# OPAMP_Combo_Schema.net
KiCad netlist of a schematic drawn in Altium Designer
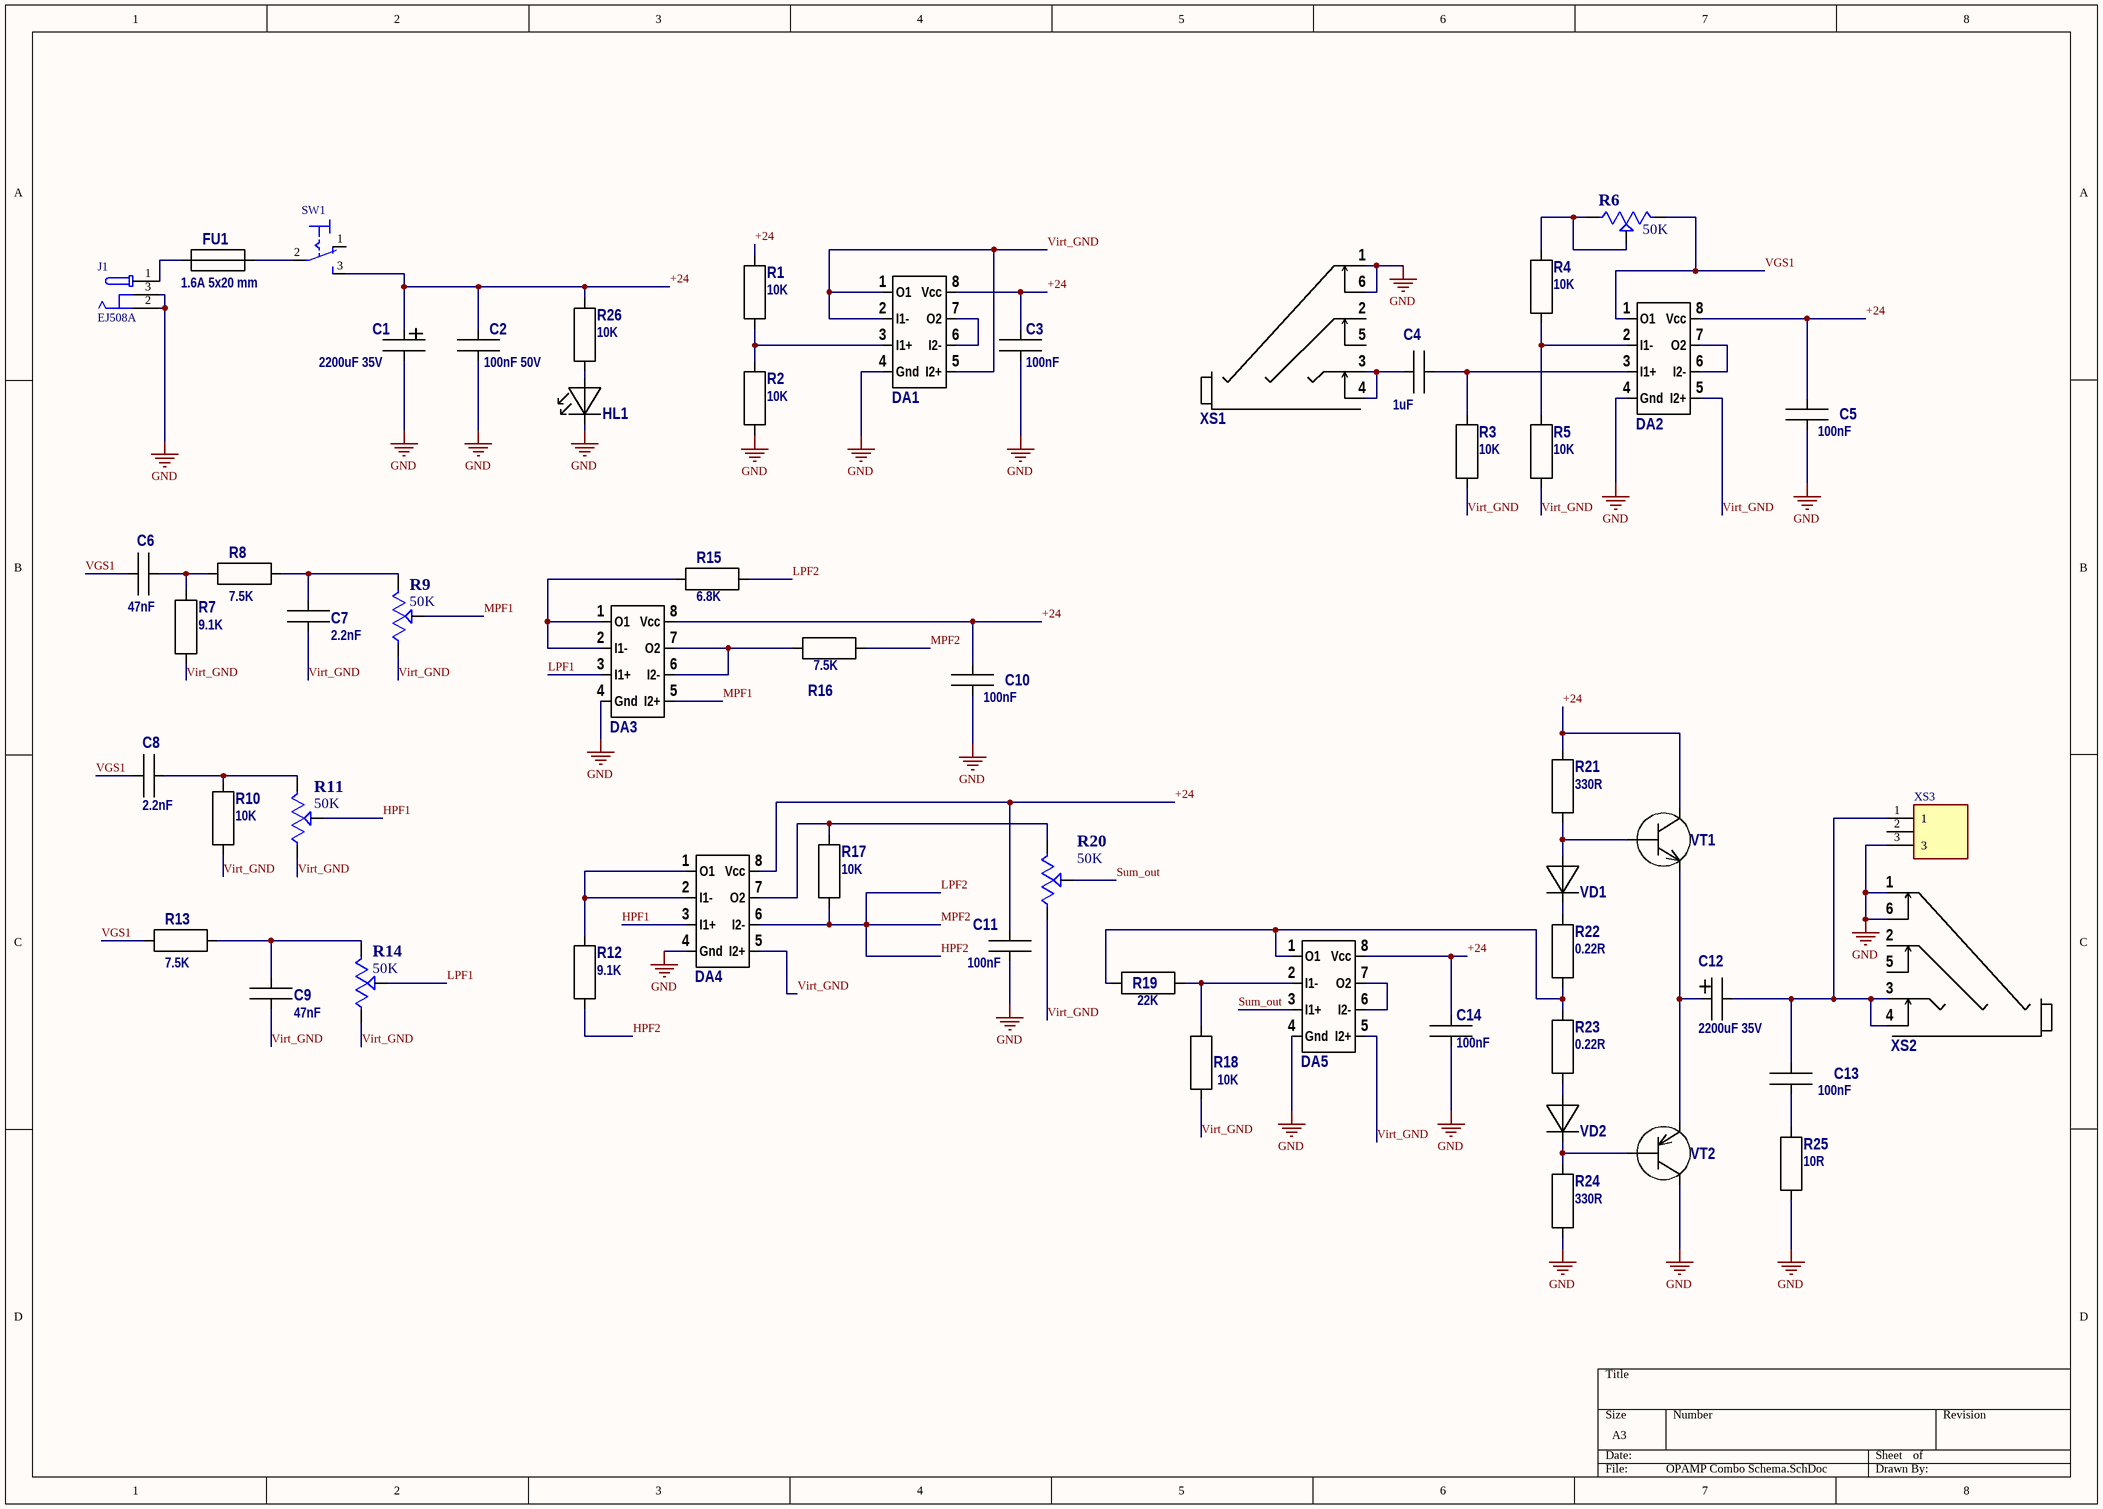
[diagram p0: OPAMP Combo Schema.SchDoc]

(export (version "E")
  (design (tool "Eeschema 10.0.6"))
  (components
    (comp (ref "C1")
      (value "2200uF 35V")
      (footprint "capr- 7.5D16.5H35")
      (description "Конденсатор алюминиевый радиальный")
      (libsource (lib "RLC V7.1_BVI") (part "C Al R"))
    )
    (comp (ref "C2")
      (value "100nF 50V")
      (footprint "C__s 5-d 8-t4")
      (description "Конденсатор керамика")
      (libsource (lib "RLC V7.1_BVI") (part "C_Disk"))
    )
    (comp (ref "C3")
      (value "100nF")
      (footprint "Cap 0805 3D")
      (description "Конденсатор керамика")
      (libsource (lib "RLC V7.1_BVI") (part "C"))
    )
    (comp (ref "C4")
      (value "1uF")
      (footprint "C__s 5-d 5.5-t4")
      (description "Конденсатор керамика")
      (libsource (lib "RLC V7.1_BVI") (part "C_Disk"))
    )
    (comp (ref "C5")
      (value "100nF")
      (footprint "Cap 0805 3D")
      (description "Конденсатор керамика")
      (libsource (lib "RLC V7.1_BVI") (part "C"))
    )
    (comp (ref "C6")
      (value "47nF")
      (footprint "C__s10-d12.4-t4")
      (description "Конденсатор керамика")
      (libsource (lib "RLC V7.1_BVI") (part "C_Disk"))
    )
    (comp (ref "C7")
      (value "2.2nF")
      (footprint "C__s10-d12.4-t4")
      (description "Конденсатор керамика")
      (libsource (lib "RLC V7.1_BVI") (part "C_Disk"))
    )
    (comp (ref "C8")
      (value "2.2nF")
      (footprint "C__s10-d12.4-t4")
      (description "Конденсатор керамика")
      (libsource (lib "RLC V7.1_BVI") (part "C_Disk"))
    )
    (comp (ref "C9")
      (value "47nF")
      (footprint "C__s10-d12.4-t4")
      (description "Конденсатор керамика")
      (libsource (lib "RLC V7.1_BVI") (part "C_Disk"))
    )
    (comp (ref "C10")
      (value "100nF")
      (footprint "Cap 0805 3D")
      (description "Конденсатор керамика")
      (libsource (lib "RLC V7.1_BVI") (part "C"))
    )
    (comp (ref "C11")
      (value "100nF")
      (footprint "Cap 0805 3D")
      (description "Конденсатор керамика")
      (libsource (lib "RLC V7.1_BVI") (part "C"))
    )
    (comp (ref "C12")
      (value "2200uF 35V")
      (footprint "capr- 7.5D16.5H35")
      (description "Конденсатор алюминиевый радиальный")
      (libsource (lib "RLC V7.1_BVI") (part "C Al R"))
    )
    (comp (ref "C13")
      (value "100nF")
      (footprint "C__s 5-d 7-t4")
      (description "Конденсатор керамика")
      (libsource (lib "RLC V7.1_BVI") (part "C_Disk"))
    )
    (comp (ref "C14")
      (value "100nF")
      (footprint "Cap 0805 3D")
      (description "Конденсатор керамика")
      (libsource (lib "RLC V7.1_BVI") (part "C"))
    )
    (comp (ref "DA1")
      (value "ОУ х 2 (1)")
      (footprint "DIP-8")
      (description "NJM4558/4559  LM158х   LM258х   LM358х   LM2904х  TL072х   NE5532x   SA5532x  и другие")
      (libsource (lib "DA V5.1_BVI") (part "ОУ х 2 (1)"))
    )
    (comp (ref "DA2")
      (value "ОУ х 2 (1)")
      (footprint "DIP-8")
      (description "NJM4558/4559  LM158х   LM258х   LM358х   LM2904х  TL072х   NE5532x   SA5532x  и другие")
      (libsource (lib "DA V5.1_BVI") (part "ОУ х 2 (1)"))
    )
    (comp (ref "DA3")
      (value "ОУ х 2 (1)")
      (footprint "DIP-8")
      (description "NJM4558/4559  LM158х   LM258х   LM358х   LM2904х  TL072х   NE5532x   SA5532x  и другие")
      (libsource (lib "DA V5.1_BVI") (part "ОУ х 2 (1)"))
    )
    (comp (ref "DA4")
      (value "ОУ х 2 (1)")
      (footprint "DIP-8")
      (description "NJM4558/4559  LM158х   LM258х   LM358х   LM2904х  TL072х   NE5532x   SA5532x  и другие")
      (libsource (lib "DA V5.1_BVI") (part "ОУ х 2 (1)"))
    )
    (comp (ref "DA5")
      (value "ОУ х 2 (1)")
      (footprint "DIP-8")
      (description "NJM4558/4559  LM158х   LM258х   LM358х   LM2904х  TL072х   NE5532x   SA5532x  и другие")
      (libsource (lib "DA V5.1_BVI") (part "ОУ х 2 (1)"))
    )
    (comp (ref "FU1")
      (value "1.6A 5x20 mm")
      (footprint "FU_FC-001-N(DH)")
      (description "Предохранитель плавкий с держателем.")
      (libsource (lib "RLC V7.1_BVI") (part "FU + Clip"))
    )
    (comp (ref "HL1")
      (value "???")
      (footprint "СД_D5_8.6_Y кр")
      (description "Св. д. D5 H8.6")
      (libsource (lib "HL Светодиоды_V2.6 BVI") (part "D5  H8.6"))
    )
    (comp (ref "J1")
      (value "EJ508A")
      (footprint "MPD_EJ508A")
      (description "Power Barrel Connector Jack 2.10mm ID _0.083_, 5.50mm OD _0.217_ Through Hole, Right Angle")
      (fields (field (name "MF") "MPD"))
      (libsource (lib "EJ508A") (part "EJ508A"))
    )
    (comp (ref "R1")
      (value "10K")
      (footprint "Res_0805 3D")
      (description "0805 10K")
      (libsource (lib "RLC V7.1_BVI") (part "R"))
    )
    (comp (ref "R2")
      (value "10K")
      (footprint "Res_0805 3D")
      (description "0805 10K")
      (libsource (lib "RLC V7.1_BVI") (part "R"))
    )
    (comp (ref "R3")
      (value "10K")
      (footprint "RES 0.25  L10")
      (description "0805 10K")
      (libsource (lib "RLC V7.1_BVI") (part "R"))
    )
    (comp (ref "R4")
      (value "10K")
      (footprint "RES 0.25  L10")
      (description "R4")
      (libsource (lib "RLC V7.1_BVI") (part "R"))
    )
    (comp (ref "R5")
      (value "10K")
      (footprint "RES 0.25  L10")
      (description "R4")
      (libsource (lib "RLC V7.1_BVI") (part "R"))
    )
    (comp (ref "R6")
      (value "50K")
      (footprint "TRIM_WH148-1A-2-18T-L20")
      (description "16mm Rotary Potentiometers")
      (fields (field (name "MF") "Kls electronics") (field (name "MP") "WH148-1A-2-18T-L20"))
      (libsource (lib "potentiometer") (part "WH148-1A-2-18T-L20"))
    )
    (comp (ref "R7")
      (value "9.1K")
      (footprint "RES 0.25  L10")
      (description "R4")
      (libsource (lib "RLC V7.1_BVI") (part "R"))
    )
    (comp (ref "R8")
      (value "7.5K")
      (footprint "RES 0.25  L10")
      (description "R4")
      (libsource (lib "RLC V7.1_BVI") (part "R"))
    )
    (comp (ref "R9")
      (value "50K")
      (footprint "TRIM_WH148-1A-2-18T-L20")
      (description "16mm Rotary Potentiometers")
      (fields (field (name "MF") "Kls electronics") (field (name "MP") "WH148-1A-2-18T-L20"))
      (libsource (lib "potentiometer") (part "WH148-1A-2-18T-L20"))
    )
    (comp (ref "R10")
      (value "10K")
      (footprint "RES 0.25  L10")
      (description "R4")
      (libsource (lib "RLC V7.1_BVI") (part "R"))
    )
    (comp (ref "R11")
      (value "50K")
      (footprint "TRIM_WH148-1A-2-18T-L20")
      (description "16mm Rotary Potentiometers")
      (fields (field (name "MF") "Kls electronics") (field (name "MP") "WH148-1A-2-18T-L20"))
      (libsource (lib "potentiometer") (part "WH148-1A-2-18T-L20"))
    )
    (comp (ref "R12")
      (value "9.1K")
      (footprint "RES 0.25  L 5")
      (description "R4")
      (libsource (lib "RLC V7.1_BVI") (part "R"))
    )
    (comp (ref "R13")
      (value "7.5K")
      (footprint "RES 0.25  L10")
      (description "R4")
      (libsource (lib "RLC V7.1_BVI") (part "R"))
    )
    (comp (ref "R14")
      (value "50K")
      (footprint "TRIM_WH148-1A-2-18T-L20")
      (description "16mm Rotary Potentiometers")
      (fields (field (name "MF") "Kls electronics") (field (name "MP") "WH148-1A-2-18T-L20"))
      (libsource (lib "potentiometer") (part "WH148-1A-2-18T-L20"))
    )
    (comp (ref "R15")
      (value "6.8K")
      (footprint "RES 0.25  L 3,75")
      (description "R4")
      (libsource (lib "RLC V7.1_BVI") (part "R"))
    )
    (comp (ref "R16")
      (value "7.5K")
      (footprint "RES 0.25  L 3,75")
      (description "R4")
      (libsource (lib "RLC V7.1_BVI") (part "R"))
    )
    (comp (ref "R17")
      (value "10K")
      (footprint "RES 0.25  L 3,75")
      (description "R4")
      (libsource (lib "RLC V7.1_BVI") (part "R"))
    )
    (comp (ref "R18")
      (value "10K")
      (footprint "RES 0.25  L10")
      (description "Резисторы плёночные (SMD; МЛТ; С2-33Н; MP9xxx)")
      (libsource (lib "RLC V7.1_BVI") (part "R"))
    )
    (comp (ref "R19")
      (value "22K")
      (footprint "RES 0.25  L10")
      (description "Резисторы плёночные (SMD; МЛТ; С2-33Н; MP9xxx)")
      (libsource (lib "RLC V7.1_BVI") (part "R"))
    )
    (comp (ref "R20")
      (value "50K")
      (footprint "TRIM_WH148-1A-2-18T-L20")
      (description "16mm Rotary Potentiometers")
      (fields (field (name "MF") "Kls electronics") (field (name "MP") "WH148-1A-2-18T-L20"))
      (libsource (lib "potentiometer") (part "WH148-1A-2-18T-L20"))
    )
    (comp (ref "R21")
      (value "330R")
      (footprint "RES 0.5  L12,5")
      (description "R4")
      (libsource (lib "RLC V7.1_BVI") (part "R"))
    )
    (comp (ref "R22")
      (value "0.22R")
      (footprint "RES 0.25  L10")
      (description "R4")
      (libsource (lib "RLC V7.1_BVI") (part "R"))
    )
    (comp (ref "R23")
      (value "0.22R")
      (footprint "RES 0.25  L10")
      (description "R4")
      (libsource (lib "RLC V7.1_BVI") (part "R"))
    )
    (comp (ref "R24")
      (value "330R")
      (footprint "RES 0.5  L12,5")
      (description "R4")
      (libsource (lib "RLC V7.1_BVI") (part "R"))
    )
    (comp (ref "R25")
      (value "10R")
      (footprint "RES 0.25  L 5")
      (description "R4")
      (libsource (lib "RLC V7.1_BVI") (part "R"))
    )
    (comp (ref "R26")
      (value "10K")
      (footprint "Res_0805 3D")
      (description "0805 10K")
      (libsource (lib "RLC V7.1_BVI") (part "R"))
    )
    (comp (ref "SW1")
      (value "MTS103")
      (footprint "MTS103")
      (description "SW TOG 1P2T 6A ON-OFF-ON MINI SOL THR")
      (fields (field (name "MF") "Not Specified") (field (name "MP") "MTS-103"))
      (libsource (lib "MTS103") (part "MTS103"))
    )
    (comp (ref "VD1")
      (value "Диод.  x1  (2)")
      (footprint "DO-35  (7.5)")
      (description "Диод  одиночный")
      (libsource (lib "VD_VT_V6.3 BVI") (part "Диод.  x1  (2)"))
    )
    (comp (ref "VD2")
      (value "Диод.  x1  (2)")
      (footprint "DO-35  (7.5)")
      (description "Диод  одиночный")
      (libsource (lib "VD_VT_V6.3 BVI") (part "Диод.  x1  (2)"))
    )
    (comp (ref "VT1")
      (value "VT NPN")
      (footprint "TO-220 (Z)")
      (description "Транзистор NPN")
      (libsource (lib "VD_VT_V6.3 BVI") (part "VT NPN"))
    )
    (comp (ref "VT2")
      (value "VT PNP")
      (footprint "TO-220 (Z)")
      (description "Транзистор PNP")
      (libsource (lib "VD_VT_V6.3 BVI") (part "VT PNP"))
    )
    (comp (ref "XS1")
      (value "NYS215")
      (footprint "Гнездо  NYS215")
      (description "Гнездо аудио стерео")
      (libsource (lib "Лампы") (part "NYS 215"))
    )
    (comp (ref "XS2")
      (value "NYS215")
      (footprint "Гнездо  NYS215")
      (description "Гнездо аудио стерео")
      (libsource (lib "Лампы") (part "NYS 215"))
    )
    (comp (ref "XS3")
      (value "MKDSN2,5/3-5.08")
      (footprint "PHOENIX_MKDSN2,5/3-5.08")
      (fields (field (name "MF") "Phoenix Contact"))
      (libsource (lib "MKDSN2_5_3-5.08") (part "MKDSN2,5/3-5.08"))
    )
  )
  (nets
    (net (code "1") (name "/+24") (class "Default")
      (node (ref "C1") (pin "2") (pinfunction "+_2") (pintype "passive"))
      (node (ref "C10") (pin "1") (pintype "passive"))
      (node (ref "C11") (pin "1") (pintype "passive"))
      (node (ref "C14") (pin "1") (pintype "passive"))
      (node (ref "C2") (pin "1") (pintype "passive"))
      (node (ref "C3") (pin "1") (pintype "passive"))
      (node (ref "C5") (pin "1") (pintype "passive"))
      (node (ref "DA1") (pin "8") (pinfunction "Vcc_8") (pintype "passive"))
      (node (ref "DA2") (pin "8") (pinfunction "Vcc_8") (pintype "passive"))
      (node (ref "DA3") (pin "8") (pinfunction "Vcc_8") (pintype "passive"))
      (node (ref "DA4") (pin "8") (pinfunction "Vcc_8") (pintype "passive"))
      (node (ref "DA5") (pin "8") (pinfunction "Vcc_8") (pintype "passive"))
      (node (ref "R1") (pin "2") (pintype "passive"))
      (node (ref "R21") (pin "2") (pintype "passive"))
      (node (ref "R26") (pin "2") (pintype "passive"))
      (node (ref "SW1") (pin "3") (pinfunction "S_3") (pintype "passive"))
      (node (ref "VT1") (pin "2") (pinfunction "C_2") (pintype "passive"))
    )
    (net (code "2") (name "/HPF1") (class "Default")
      (node (ref "DA4") (pin "3") (pinfunction "I1+_3") (pintype "passive"))
      (node (ref "R11") (pin "2") (pinfunction "2_2") (pintype "passive"))
    )
    (net (code "3") (name "/HPF2") (class "Default")
      (node (ref "DA4") (pin "6") (pinfunction "I2-_6") (pintype "passive"))
      (node (ref "R12") (pin "1") (pintype "passive"))
      (node (ref "R15") (pin "2") (pintype "passive"))
      (node (ref "R16") (pin "2") (pintype "passive"))
      (node (ref "R17") (pin "1") (pintype "passive"))
    )
    (net (code "4") (name "/LPF1") (class "Default")
      (node (ref "DA3") (pin "3") (pinfunction "I1+_3") (pintype "passive"))
      (node (ref "R14") (pin "2") (pinfunction "2_2") (pintype "passive"))
    )
    (net (code "5") (name "/MPF1") (class "Default")
      (node (ref "DA3") (pin "5") (pinfunction "I2+_5") (pintype "passive"))
      (node (ref "R9") (pin "2") (pinfunction "2_2") (pintype "passive"))
    )
    (net (code "6") (name "/Sum_out") (class "Default")
      (node (ref "DA5") (pin "3") (pinfunction "I1+_3") (pintype "passive"))
      (node (ref "R20") (pin "2") (pinfunction "2_2") (pintype "passive"))
    )
    (net (code "7") (name "/VGS1") (class "Default")
      (node (ref "C6") (pin "1") (pintype "passive"))
      (node (ref "C8") (pin "2") (pintype "passive"))
      (node (ref "DA2") (pin "1") (pinfunction "O1_1") (pintype "passive"))
      (node (ref "R13") (pin "1") (pintype "passive"))
      (node (ref "R6") (pin "3") (pinfunction "3_3") (pintype "passive"))
    )
    (net (code "8") (name "/Virt_GND") (class "Default")
      (node (ref "C7") (pin "1") (pintype "passive"))
      (node (ref "C9") (pin "1") (pintype "passive"))
      (node (ref "DA1") (pin "1") (pinfunction "O1_1") (pintype "passive"))
      (node (ref "DA1") (pin "2") (pinfunction "I1-_2") (pintype "passive"))
      (node (ref "DA1") (pin "5") (pinfunction "I2+_5") (pintype "passive"))
      (node (ref "DA2") (pin "5") (pinfunction "I2+_5") (pintype "passive"))
      (node (ref "DA4") (pin "5") (pinfunction "I2+_5") (pintype "passive"))
      (node (ref "DA5") (pin "5") (pinfunction "I2+_5") (pintype "passive"))
      (node (ref "R10") (pin "2") (pintype "passive"))
      (node (ref "R11") (pin "1") (pinfunction "1_1") (pintype "passive"))
      (node (ref "R14") (pin "1") (pinfunction "1_1") (pintype "passive"))
      (node (ref "R18") (pin "1") (pintype "passive"))
      (node (ref "R20") (pin "3") (pinfunction "3_3") (pintype "passive"))
      (node (ref "R3") (pin "1") (pintype "passive"))
      (node (ref "R5") (pin "2") (pintype "passive"))
      (node (ref "R7") (pin "1") (pintype "passive"))
      (node (ref "R9") (pin "1") (pinfunction "1_1") (pintype "passive"))
    )
    (net (code "9") (name "GND") (class "Default")
      (node (ref "C1") (pin "1") (pinfunction "-_1") (pintype "passive"))
      (node (ref "C10") (pin "2") (pintype "passive"))
      (node (ref "C11") (pin "2") (pintype "passive"))
      (node (ref "C14") (pin "2") (pintype "passive"))
      (node (ref "C2") (pin "2") (pintype "passive"))
      (node (ref "C3") (pin "2") (pintype "passive"))
      (node (ref "C5") (pin "2") (pintype "passive"))
      (node (ref "DA1") (pin "4") (pinfunction "Gnd_4") (pintype "passive"))
      (node (ref "DA2") (pin "4") (pinfunction "Gnd_4") (pintype "passive"))
      (node (ref "DA3") (pin "4") (pinfunction "Gnd_4") (pintype "passive"))
      (node (ref "DA4") (pin "4") (pinfunction "Gnd_4") (pintype "passive"))
      (node (ref "DA5") (pin "4") (pinfunction "Gnd_4") (pintype "passive"))
      (node (ref "HL1") (pin "1") (pinfunction "K_1") (pintype "passive"))
      (node (ref "J1") (pin "2") (pinfunction "2_2") (pintype "passive"))
      (node (ref "J1") (pin "3") (pinfunction "3_3") (pintype "passive"))
      (node (ref "R2") (pin "1") (pintype "passive"))
      (node (ref "R24") (pin "1") (pintype "passive"))
      (node (ref "R25") (pin "1") (pintype "passive"))
      (node (ref "VT2") (pin "2") (pinfunction "C_2") (pintype "passive"))
      (node (ref "XS1") (pin "1") (pintype "passive"))
      (node (ref "XS1") (pin "6") (pintype "passive"))
      (node (ref "XS2") (pin "1") (pintype "passive"))
      (node (ref "XS2") (pin "6") (pintype "passive"))
      (node (ref "XS3") (pin "3") (pinfunction "3_3") (pintype "passive"))
    )
    (net (code "10") (name "Net-(C4-Pad2)") (class "Default")
      (node (ref "C4") (pin "2") (pintype "passive"))
      (node (ref "XS1") (pin "3") (pintype "passive"))
      (node (ref "XS1") (pin "4") (pintype "passive"))
    )
    (net (code "11") (name "Net-(C6-Pad2)") (class "Default")
      (node (ref "C6") (pin "2") (pintype "passive"))
      (node (ref "R7") (pin "2") (pintype "passive"))
      (node (ref "R8") (pin "1") (pintype "passive"))
    )
    (net (code "12") (name "Net-(C7-Pad2)") (class "Default")
      (node (ref "C7") (pin "2") (pintype "passive"))
      (node (ref "R8") (pin "2") (pintype "passive"))
      (node (ref "R9") (pin "3") (pinfunction "3_3") (pintype "passive"))
    )
    (net (code "13") (name "Net-(C8-Pad1)") (class "Default")
      (node (ref "C8") (pin "1") (pintype "passive"))
      (node (ref "R10") (pin "1") (pintype "passive"))
      (node (ref "R11") (pin "3") (pinfunction "3_3") (pintype "passive"))
    )
    (net (code "14") (name "Net-(C9-Pad2)") (class "Default")
      (node (ref "C9") (pin "2") (pintype "passive"))
      (node (ref "R13") (pin "2") (pintype "passive"))
      (node (ref "R14") (pin "3") (pinfunction "3_3") (pintype "passive"))
    )
    (net (code "15") (name "Net-(C12-+)") (class "Default")
      (node (ref "C12") (pin "2") (pinfunction "+_2") (pintype "passive"))
      (node (ref "VT1") (pin "3") (pinfunction "E_3") (pintype "passive"))
      (node (ref "VT2") (pin "3") (pinfunction "E_3") (pintype "passive"))
    )
    (net (code "16") (name "Net-(C12--)") (class "Default")
      (node (ref "C12") (pin "1") (pinfunction "-_1") (pintype "passive"))
      (node (ref "C13") (pin "1") (pintype "passive"))
      (node (ref "XS2") (pin "3") (pintype "passive"))
      (node (ref "XS2") (pin "4") (pintype "passive"))
      (node (ref "XS3") (pin "1") (pinfunction "1_1") (pintype "passive"))
    )
    (net (code "17") (name "Net-(C13-Pad2)") (class "Default")
      (node (ref "C13") (pin "2") (pintype "passive"))
      (node (ref "R25") (pin "2") (pintype "passive"))
    )
    (net (code "18") (name "Net-(DA1-I1+)") (class "Default")
      (node (ref "DA1") (pin "3") (pinfunction "I1+_3") (pintype "passive"))
      (node (ref "R1") (pin "1") (pintype "passive"))
      (node (ref "R2") (pin "2") (pintype "passive"))
    )
    (net (code "19") (name "Net-(DA1-I2-)") (class "Default")
      (node (ref "DA1") (pin "6") (pinfunction "I2-_6") (pintype "passive"))
      (node (ref "DA1") (pin "7") (pinfunction "O2_7") (pintype "passive"))
    )
    (net (code "20") (name "Net-(DA2-I1+)") (class "Default")
      (node (ref "C4") (pin "1") (pintype "passive"))
      (node (ref "DA2") (pin "3") (pinfunction "I1+_3") (pintype "passive"))
      (node (ref "R3") (pin "2") (pintype "passive"))
    )
    (net (code "21") (name "Net-(DA2-I1-)") (class "Default")
      (node (ref "DA2") (pin "2") (pinfunction "I1-_2") (pintype "passive"))
      (node (ref "R4") (pin "2") (pintype "passive"))
      (node (ref "R5") (pin "1") (pintype "passive"))
    )
    (net (code "22") (name "Net-(DA2-I2-)") (class "Default")
      (node (ref "DA2") (pin "6") (pinfunction "I2-_6") (pintype "passive"))
      (node (ref "DA2") (pin "7") (pinfunction "O2_7") (pintype "passive"))
    )
    (net (code "23") (name "Net-(DA3-I1-)") (class "Default")
      (node (ref "DA3") (pin "1") (pinfunction "O1_1") (pintype "passive"))
      (node (ref "DA3") (pin "2") (pinfunction "I1-_2") (pintype "passive"))
      (node (ref "R15") (pin "1") (pintype "passive"))
    )
    (net (code "24") (name "Net-(DA3-I2-)") (class "Default")
      (node (ref "DA3") (pin "6") (pinfunction "I2-_6") (pintype "passive"))
      (node (ref "DA3") (pin "7") (pinfunction "O2_7") (pintype "passive"))
      (node (ref "R16") (pin "1") (pintype "passive"))
    )
    (net (code "25") (name "Net-(DA4-I1-)") (class "Default")
      (node (ref "DA4") (pin "1") (pinfunction "O1_1") (pintype "passive"))
      (node (ref "DA4") (pin "2") (pinfunction "I1-_2") (pintype "passive"))
      (node (ref "R12") (pin "2") (pintype "passive"))
    )
    (net (code "26") (name "Net-(DA4-O2)") (class "Default")
      (node (ref "DA4") (pin "7") (pinfunction "O2_7") (pintype "passive"))
      (node (ref "R17") (pin "2") (pintype "passive"))
      (node (ref "R20") (pin "1") (pinfunction "1_1") (pintype "passive"))
    )
    (net (code "27") (name "Net-(DA5-I1-)") (class "Default")
      (node (ref "DA5") (pin "2") (pinfunction "I1-_2") (pintype "passive"))
      (node (ref "R18") (pin "2") (pintype "passive"))
      (node (ref "R19") (pin "2") (pintype "passive"))
    )
    (net (code "28") (name "Net-(DA5-I2-)") (class "Default")
      (node (ref "DA5") (pin "6") (pinfunction "I2-_6") (pintype "passive"))
      (node (ref "DA5") (pin "7") (pinfunction "O2_7") (pintype "passive"))
    )
    (net (code "29") (name "Net-(DA5-O1)") (class "Default")
      (node (ref "DA5") (pin "1") (pinfunction "O1_1") (pintype "passive"))
      (node (ref "R19") (pin "1") (pintype "passive"))
      (node (ref "R22") (pin "2") (pintype "passive"))
      (node (ref "R23") (pin "2") (pintype "passive"))
    )
    (net (code "30") (name "Net-(FU1-Pad1)") (class "Default")
      (node (ref "FU1") (pin "1") (pintype "passive"))
      (node (ref "J1") (pin "1") (pinfunction "1_1") (pintype "passive"))
    )
    (net (code "31") (name "Net-(HL1-A)") (class "Default")
      (node (ref "HL1") (pin "2") (pinfunction "A_2") (pintype "passive"))
      (node (ref "R26") (pin "1") (pintype "passive"))
    )
    (net (code "32") (name "Net-(R4-Pad1)") (class "Default")
      (node (ref "R4") (pin "1") (pintype "passive"))
      (node (ref "R6") (pin "1") (pinfunction "1_1") (pintype "passive"))
      (node (ref "R6") (pin "2") (pinfunction "2_2") (pintype "passive"))
    )
    (net (code "33") (name "Net-(SW1-P)") (class "Default")
      (node (ref "FU1") (pin "2") (pintype "passive"))
      (node (ref "SW1") (pin "2") (pinfunction "P_2") (pintype "passive"))
    )
    (net (code "34") (name "Net-(VD1-A)") (class "Default")
      (node (ref "R21") (pin "1") (pintype "passive"))
      (node (ref "VD1") (pin "2") (pinfunction "A_2") (pintype "passive"))
      (node (ref "VT1") (pin "1") (pinfunction "B_1") (pintype "passive"))
    )
    (net (code "35") (name "Net-(VD1-K)") (class "Default")
      (node (ref "R22") (pin "1") (pintype "passive"))
      (node (ref "VD1") (pin "1") (pinfunction "K_1") (pintype "passive"))
    )
    (net (code "36") (name "Net-(VD2-A)") (class "Default")
      (node (ref "R23") (pin "1") (pintype "passive"))
      (node (ref "VD2") (pin "2") (pinfunction "A_2") (pintype "passive"))
    )
    (net (code "37") (name "Net-(VD2-K)") (class "Default")
      (node (ref "R24") (pin "2") (pintype "passive"))
      (node (ref "VD2") (pin "1") (pinfunction "K_1") (pintype "passive"))
      (node (ref "VT2") (pin "1") (pinfunction "B_1") (pintype "passive"))
    )
    (net (code "38") (name "unconnected-(SW1-O-Pad1)") (class "Default")
      (node (ref "SW1") (pin "1") (pinfunction "O_1") (pintype "passive"))
    )
    (net (code "39") (name "unconnected-(XS1-Pad2)") (class "Default")
      (node (ref "XS1") (pin "2") (pintype "passive"))
    )
    (net (code "40") (name "unconnected-(XS1-Pad5)") (class "Default")
      (node (ref "XS1") (pin "5") (pintype "passive"))
    )
    (net (code "41") (name "unconnected-(XS2-Pad2)") (class "Default")
      (node (ref "XS2") (pin "2") (pintype "passive"))
    )
    (net (code "42") (name "unconnected-(XS2-Pad5)") (class "Default")
      (node (ref "XS2") (pin "5") (pintype "passive"))
    )
    (net (code "43") (name "unconnected-(XS3-Pad2)") (class "Default")
      (node (ref "XS3") (pin "2") (pinfunction "2_2") (pintype "passive"))
    )
  )
)
